# Sheet1.net
KiCad netlist of a schematic drawn in Altium Designer
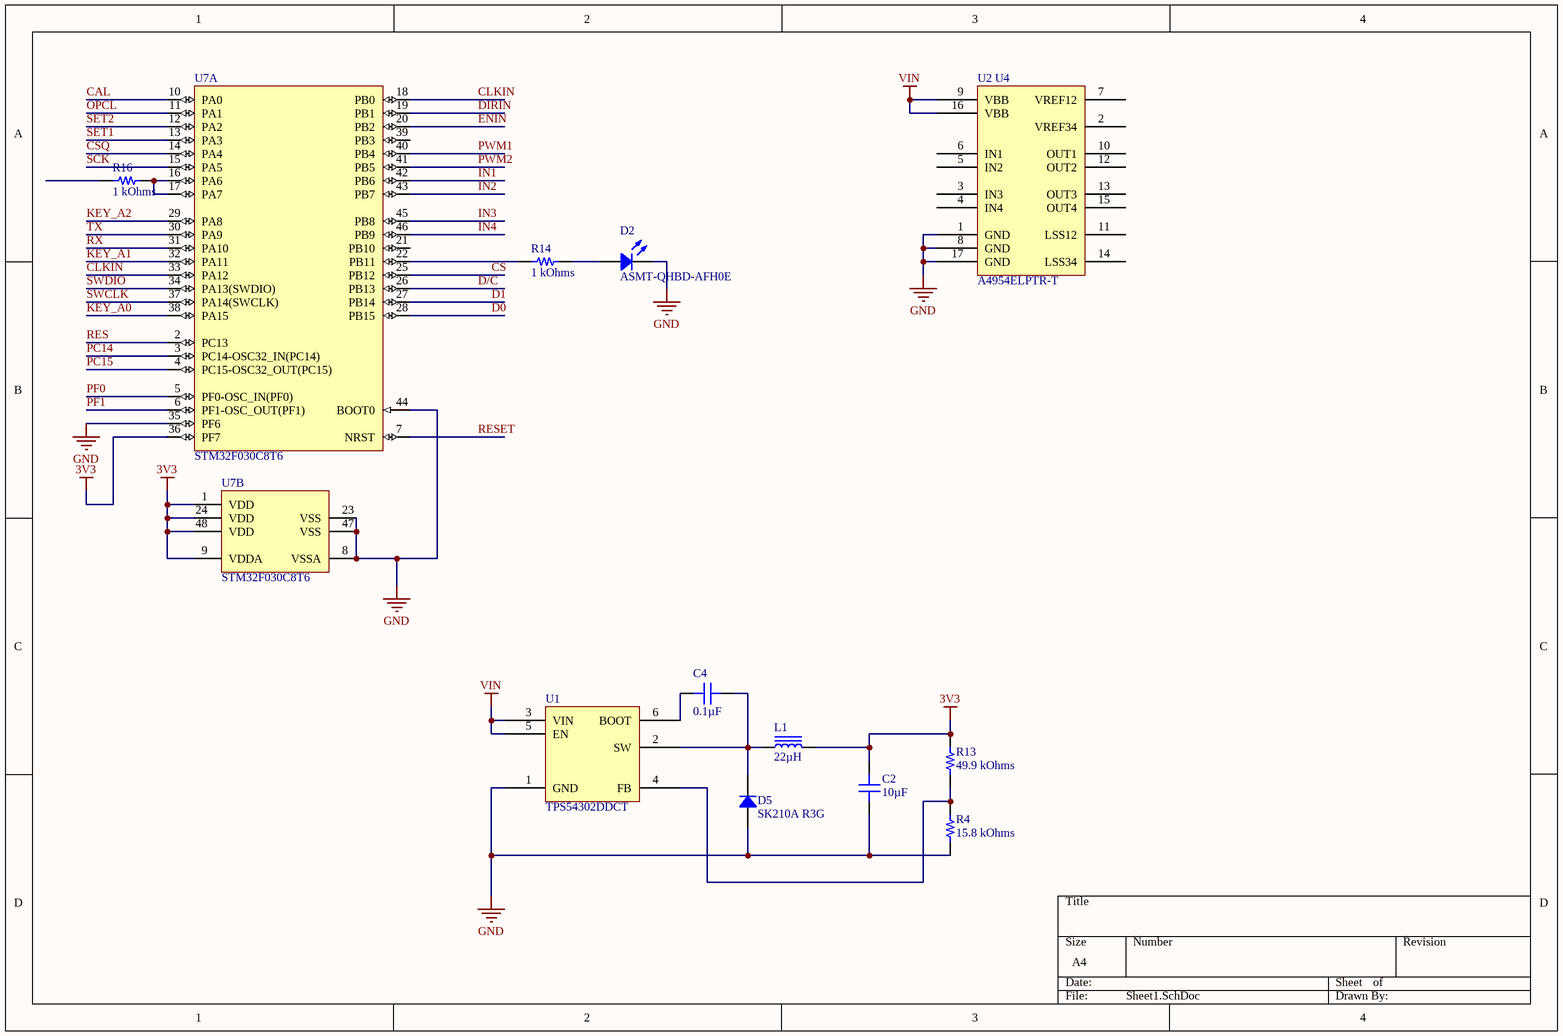
[diagram p0: Sheet1.SchDoc]

(export (version "E")
  (design (tool "Eeschema 10.0.6"))
  (components
    (comp (ref "C2")
      (value "10µF")
      (footprint "CAP 0805_2012")
      (description "CAP CER 10UF 25V JB 0805")
      (fields
        (field (name "PART NUMBER") "C2012JB1E106M085AC")
        (field (name "MANUFACTURER") "TDK Corporation")
      )
      (libsource (lib "Celestial Altium Library - altium_library") (part "Capacitor"))
    )
    (comp (ref "C4")
      (value "0.1µF")
      (footprint "CAP 0805_2012")
      (description "CAP CER 0.1UF 50V X7R 0805")
      (fields (field (name "PART NUMBER") "CC0805MRX7R9BB104") (field (name "MANUFACTURER") "Yageo"))
      (libsource (lib "Celestial Altium Library - altium_library") (part "Capacitor"))
    )
    (comp (ref "D2")
      (value "ASMT-QHBD-AFH0E")
      (footprint "Broadcom 4-PLLC 3228")
      (description "LED INDICATOR 0.5W RED/ORN 4PLCC")
      (fields (field (name "MANUFACTURER") "Broadcom Limited"))
      (libsource (lib "Celestial Altium Library - altium_library") (part "LED"))
    )
    (comp (ref "D5")
      (value "SK210A R3G")
      (footprint "DO214AC SMA")
      (description "DIODE SCHOTTKY 100V 2A DO214AC")
      (fields (field (name "MANUFACTURER") "Taiwan Semiconductor Corporation"))
      (libsource (lib "Celestial Altium Library - altium_library") (part "Diode"))
    )
    (comp (ref "L1")
      (value "22µH")
      (footprint "TDK VLCF4024-2")
      (description "FIXED IND 22UH 590MA 188 MOHM")
      (fields
        (field (name "PART NUMBER") "VLCF5024T-220MR59-2")
        (field (name "MANUFACTURER") "TDK Corporation")
      )
      (libsource (lib "Celestial Altium Library - altium_library") (part "Inductor"))
    )
    (comp (ref "R4")
      (value "15.8 kOhms")
      (footprint "RES 0805_2012")
      (description "RES 15.8K OHM 0.1% 1/8W 0805")
      (fields
        (field (name "PART NUMBER") "ERA-6AEB1582V")
        (field (name "MANUFACTURER") "Panasonic Electronic Components")
      )
      (libsource (lib "Celestial Altium Library - altium_library") (part "Resistor"))
    )
    (comp (ref "R13")
      (value "49.9 kOhms")
      (footprint "RES 0805_2012")
      (description "RES SMD 49.9K OHM 0.1% 1/4W 0805")
      (fields
        (field (name "PART NUMBER") "6-2176093-6")
        (field (name "MANUFACTURER") "TE Connectivity Passive Product")
      )
      (libsource (lib "Celestial Altium Library - altium_library") (part "Resistor"))
    )
    (comp (ref "R14")
      (value "1 kOhms")
      (footprint "RES 0805_2012")
      (description "RES SMD 1K OHM 0.1% 1/10W 0805")
      (fields
        (field (name "PART NUMBER") "CPF0805B1K0E")
        (field (name "MANUFACTURER") "TE Connectivity Passive Product")
      )
      (libsource (lib "Celestial Altium Library - altium_library") (part "Resistor"))
    )
    (comp (ref "R16")
      (value "1 kOhms")
      (footprint "RES 0805_2012")
      (description "RES SMD 1K OHM 0.1% 1/10W 0805")
      (fields
        (field (name "PART NUMBER") "CPF0805B1K0E")
        (field (name "MANUFACTURER") "TE Connectivity Passive Product")
      )
      (libsource (lib "Celestial Altium Library - altium_library") (part "Resistor"))
    )
    (comp (ref "U1")
      (value "TPS54302DDCT")
      (footprint "TI SOT-23-6 DDC")
      (description "IC REG BUCK ADJ 3A TSOT23-6")
      (fields (field (name "MANUFACTURER") "Texas Instruments"))
      (libsource (lib "Celestial Altium Library - altium_library") (part "TI TPS54302"))
    )
    (comp (ref "U2 U4")
      (value "A4954ELPTR-T")
      (footprint "ALLEGRO TSSOP-16EP LP")
      (description "IC MOTOR DRIVER 8V-40V 16TSSOP")
      (fields (field (name "MANUFACTURER") "Allegro MicroSystems"))
      (libsource (lib "Celestial Altium Library - altium_library") (part "Allegro A4954"))
    )
    (comp (ref "U7")
      (value "STM32F030C8T6")
      (footprint "STM-LQFP48_N")
      (libsource (lib "STMicroelectronics STM32 F0") (part "STM32F030C8T6"))
    )
  )
  (nets
    (net (code "1") (name "/CAL") (class "Default")
      (node (ref "U7") (pin "10") (pinfunction "PA0_10") (pintype "bidirectional"))
    )
    (net (code "2") (name "/CLKIN") (class "Default")
      (node (ref "U7") (pin "18") (pinfunction "PB0_18") (pintype "bidirectional"))
      (node (ref "U7") (pin "33") (pinfunction "PA12_33") (pintype "bidirectional"))
    )
    (net (code "3") (name "/CS") (class "Default")
      (node (ref "U7") (pin "25") (pinfunction "PB12_25") (pintype "bidirectional"))
    )
    (net (code "4") (name "/CSQ") (class "Default")
      (node (ref "U7") (pin "14") (pinfunction "PA4_14") (pintype "bidirectional"))
    )
    (net (code "5") (name "/D0") (class "Default")
      (node (ref "U7") (pin "28") (pinfunction "PB15_28") (pintype "bidirectional"))
    )
    (net (code "6") (name "/D1") (class "Default")
      (node (ref "U7") (pin "27") (pinfunction "PB14_27") (pintype "bidirectional"))
    )
    (net (code "7") (name "/DIRIN") (class "Default")
      (node (ref "U7") (pin "19") (pinfunction "PB1_19") (pintype "bidirectional"))
    )
    (net (code "8") (name "/D{slash}C") (class "Default")
      (node (ref "U7") (pin "26") (pinfunction "PB13_26") (pintype "bidirectional"))
    )
    (net (code "9") (name "/ENIN") (class "Default")
      (node (ref "U7") (pin "20") (pinfunction "PB2_20") (pintype "bidirectional"))
    )
    (net (code "10") (name "/IN1") (class "Default")
      (node (ref "U7") (pin "42") (pinfunction "PB6_42") (pintype "bidirectional"))
    )
    (net (code "11") (name "/IN2") (class "Default")
      (node (ref "U7") (pin "43") (pinfunction "PB7_43") (pintype "bidirectional"))
    )
    (net (code "12") (name "/IN3") (class "Default")
      (node (ref "U7") (pin "45") (pinfunction "PB8_45") (pintype "bidirectional"))
    )
    (net (code "13") (name "/IN4") (class "Default")
      (node (ref "U7") (pin "46") (pinfunction "PB9_46") (pintype "bidirectional"))
    )
    (net (code "14") (name "/KEY_A0") (class "Default")
      (node (ref "U7") (pin "38") (pinfunction "PA15_38") (pintype "bidirectional"))
    )
    (net (code "15") (name "/KEY_A1") (class "Default")
      (node (ref "U7") (pin "32") (pinfunction "PA11_32") (pintype "bidirectional"))
    )
    (net (code "16") (name "/KEY_A2") (class "Default")
      (node (ref "U7") (pin "29") (pinfunction "PA8_29") (pintype "bidirectional"))
    )
    (net (code "17") (name "/OPCL") (class "Default")
      (node (ref "U7") (pin "11") (pinfunction "PA1_11") (pintype "bidirectional"))
    )
    (net (code "18") (name "/PC14") (class "Default")
      (node (ref "U7") (pin "3") (pinfunction "PC14-OSC32_IN(PC14)_3") (pintype "bidirectional"))
    )
    (net (code "19") (name "/PC15") (class "Default")
      (node (ref "U7") (pin "4") (pinfunction "PC15-OSC32_OUT(PC15)_4") (pintype "bidirectional"))
    )
    (net (code "20") (name "/PF0") (class "Default")
      (node (ref "U7") (pin "5") (pinfunction "PF0-OSC_IN(PF0)_5") (pintype "bidirectional"))
    )
    (net (code "21") (name "/PF1") (class "Default")
      (node (ref "U7") (pin "6") (pinfunction "PF1-OSC_OUT(PF1)_6") (pintype "bidirectional"))
    )
    (net (code "22") (name "/PWM1") (class "Default")
      (node (ref "U7") (pin "40") (pinfunction "PB4_40") (pintype "bidirectional"))
    )
    (net (code "23") (name "/PWM2") (class "Default")
      (node (ref "U7") (pin "41") (pinfunction "PB5_41") (pintype "bidirectional"))
    )
    (net (code "24") (name "/RES") (class "Default")
      (node (ref "U7") (pin "2") (pinfunction "PC13_2") (pintype "bidirectional"))
    )
    (net (code "25") (name "/RESET") (class "Default")
      (node (ref "U7") (pin "7") (pinfunction "NRST_7") (pintype "bidirectional"))
    )
    (net (code "26") (name "/RX") (class "Default")
      (node (ref "U7") (pin "31") (pinfunction "PA10_31") (pintype "bidirectional"))
    )
    (net (code "27") (name "/SCK") (class "Default")
      (node (ref "U7") (pin "15") (pinfunction "PA5_15") (pintype "bidirectional"))
    )
    (net (code "28") (name "/SET1") (class "Default")
      (node (ref "U7") (pin "13") (pinfunction "PA3_13") (pintype "bidirectional"))
    )
    (net (code "29") (name "/SET2") (class "Default")
      (node (ref "U7") (pin "12") (pinfunction "PA2_12") (pintype "bidirectional"))
    )
    (net (code "30") (name "/SWCLK") (class "Default")
      (node (ref "U7") (pin "37") (pinfunction "PA14(SWCLK)_37") (pintype "bidirectional"))
    )
    (net (code "31") (name "/SWDIO") (class "Default")
      (node (ref "U7") (pin "34") (pinfunction "PA13(SWDIO)_34") (pintype "bidirectional"))
    )
    (net (code "32") (name "/TX") (class "Default")
      (node (ref "U7") (pin "30") (pinfunction "PA9_30") (pintype "bidirectional"))
    )
    (net (code "33") (name "3V3") (class "Default")
      (node (ref "C2") (pin "2") (pinfunction "2_2") (pintype "passive"))
      (node (ref "L1") (pin "2") (pinfunction "2_2") (pintype "passive"))
      (node (ref "R13") (pin "2") (pinfunction "2_2") (pintype "passive"))
      (node (ref "U7") (pin "1") (pinfunction "VDD_1") (pintype "power_in"))
      (node (ref "U7") (pin "24") (pinfunction "VDD_24") (pintype "power_in"))
      (node (ref "U7") (pin "36") (pinfunction "PF7_36") (pintype "bidirectional"))
      (node (ref "U7") (pin "48") (pinfunction "VDD_48") (pintype "power_in"))
      (node (ref "U7") (pin "9") (pinfunction "VDDA_9") (pintype "power_in"))
    )
    (net (code "34") (name "GND") (class "Default")
      (node (ref "C2") (pin "1") (pinfunction "1_1") (pintype "passive"))
      (node (ref "D2") (pin "2") (pinfunction "2_2") (pintype "passive"))
      (node (ref "D5") (pin "1") (pinfunction "1_1") (pintype "passive"))
      (node (ref "R4") (pin "1") (pinfunction "1_1") (pintype "passive"))
      (node (ref "U1") (pin "1") (pinfunction "GND_1") (pintype "passive"))
      (node (ref "U2 U4") (pin "1") (pinfunction "GND_1") (pintype "passive"))
      (node (ref "U2 U4") (pin "17") (pinfunction "GND_17") (pintype "passive"))
      (node (ref "U2 U4") (pin "8") (pinfunction "GND_8") (pintype "passive"))
      (node (ref "U7") (pin "23") (pinfunction "VSS_23") (pintype "power_in"))
      (node (ref "U7") (pin "35") (pinfunction "PF6_35") (pintype "bidirectional"))
      (node (ref "U7") (pin "44") (pinfunction "BOOT0_44") (pintype "input"))
      (node (ref "U7") (pin "47") (pinfunction "VSS_47") (pintype "power_in"))
      (node (ref "U7") (pin "8") (pinfunction "VSSA_8") (pintype "power_in"))
    )
    (net (code "35") (name "Net-(D2-Pad1)") (class "Default")
      (node (ref "D2") (pin "1") (pinfunction "1_1") (pintype "passive"))
      (node (ref "R14") (pin "2") (pinfunction "2_2") (pintype "passive"))
    )
    (net (code "36") (name "Net-(U1-BOOT)") (class "Default")
      (node (ref "C4") (pin "1") (pinfunction "1_1") (pintype "passive"))
      (node (ref "U1") (pin "6") (pinfunction "BOOT_6") (pintype "passive"))
    )
    (net (code "37") (name "Net-(U1-FB)") (class "Default")
      (node (ref "R13") (pin "1") (pinfunction "1_1") (pintype "passive"))
      (node (ref "R4") (pin "2") (pinfunction "2_2") (pintype "passive"))
      (node (ref "U1") (pin "4") (pinfunction "FB_4") (pintype "passive"))
    )
    (net (code "38") (name "Net-(U1-SW)") (class "Default")
      (node (ref "C4") (pin "2") (pinfunction "2_2") (pintype "passive"))
      (node (ref "D5") (pin "2") (pinfunction "2_2") (pintype "passive"))
      (node (ref "L1") (pin "1") (pinfunction "1_1") (pintype "passive"))
      (node (ref "U1") (pin "2") (pinfunction "SW_2") (pintype "passive"))
    )
    (net (code "39") (name "Net-(U7A-PA6)") (class "Default")
      (node (ref "R16") (pin "2") (pinfunction "2_2") (pintype "passive"))
      (node (ref "U7") (pin "16") (pinfunction "PA6_16") (pintype "bidirectional"))
      (node (ref "U7") (pin "17") (pinfunction "PA7_17") (pintype "bidirectional"))
    )
    (net (code "40") (name "Net-(U7A-PB11)") (class "Default")
      (node (ref "R14") (pin "1") (pinfunction "1_1") (pintype "passive"))
      (node (ref "U7") (pin "22") (pinfunction "PB11_22") (pintype "bidirectional"))
    )
    (net (code "41") (name "VIN") (class "Default")
      (node (ref "U1") (pin "3") (pinfunction "VIN_3") (pintype "passive"))
      (node (ref "U1") (pin "5") (pinfunction "EN_5") (pintype "passive"))
      (node (ref "U2 U4") (pin "16") (pinfunction "VBB_16") (pintype "passive"))
      (node (ref "U2 U4") (pin "9") (pinfunction "VBB_9") (pintype "passive"))
    )
    (net (code "42") (name "unconnected-(R16-Pad1)") (class "Default")
      (node (ref "R16") (pin "1") (pinfunction "1_1") (pintype "passive"))
    )
    (net (code "43") (name "unconnected-(U2 U4-IN1-Pad6)") (class "Default")
      (node (ref "U2 U4") (pin "6") (pinfunction "IN1_6") (pintype "passive"))
    )
    (net (code "44") (name "unconnected-(U2 U4-IN2-Pad5)") (class "Default")
      (node (ref "U2 U4") (pin "5") (pinfunction "IN2_5") (pintype "passive"))
    )
    (net (code "45") (name "unconnected-(U2 U4-IN3-Pad3)") (class "Default")
      (node (ref "U2 U4") (pin "3") (pinfunction "IN3_3") (pintype "passive"))
    )
    (net (code "46") (name "unconnected-(U2 U4-IN4-Pad4)") (class "Default")
      (node (ref "U2 U4") (pin "4") (pinfunction "IN4_4") (pintype "passive"))
    )
    (net (code "47") (name "unconnected-(U2 U4-LSS12-Pad11)") (class "Default")
      (node (ref "U2 U4") (pin "11") (pinfunction "LSS12_11") (pintype "passive"))
    )
    (net (code "48") (name "unconnected-(U2 U4-LSS34-Pad14)") (class "Default")
      (node (ref "U2 U4") (pin "14") (pinfunction "LSS34_14") (pintype "passive"))
    )
    (net (code "49") (name "unconnected-(U2 U4-OUT1-Pad10)") (class "Default")
      (node (ref "U2 U4") (pin "10") (pinfunction "OUT1_10") (pintype "passive"))
    )
    (net (code "50") (name "unconnected-(U2 U4-OUT2-Pad12)") (class "Default")
      (node (ref "U2 U4") (pin "12") (pinfunction "OUT2_12") (pintype "passive"))
    )
    (net (code "51") (name "unconnected-(U2 U4-OUT3-Pad13)") (class "Default")
      (node (ref "U2 U4") (pin "13") (pinfunction "OUT3_13") (pintype "passive"))
    )
    (net (code "52") (name "unconnected-(U2 U4-OUT4-Pad15)") (class "Default")
      (node (ref "U2 U4") (pin "15") (pinfunction "OUT4_15") (pintype "passive"))
    )
    (net (code "53") (name "unconnected-(U2 U4-VREF12-Pad7)") (class "Default")
      (node (ref "U2 U4") (pin "7") (pinfunction "VREF12_7") (pintype "passive"))
    )
    (net (code "54") (name "unconnected-(U2 U4-VREF34-Pad2)") (class "Default")
      (node (ref "U2 U4") (pin "2") (pinfunction "VREF34_2") (pintype "passive"))
    )
    (net (code "55") (name "unconnected-(U7A-PB3-Pad39)") (class "Default")
      (node (ref "U7") (pin "39") (pinfunction "PB3_39") (pintype "bidirectional"))
    )
    (net (code "56") (name "unconnected-(U7A-PB10-Pad21)") (class "Default")
      (node (ref "U7") (pin "21") (pinfunction "PB10_21") (pintype "bidirectional"))
    )
  )
)
